# Sheet2.net
KiCad netlist of a schematic drawn in Altium Designer
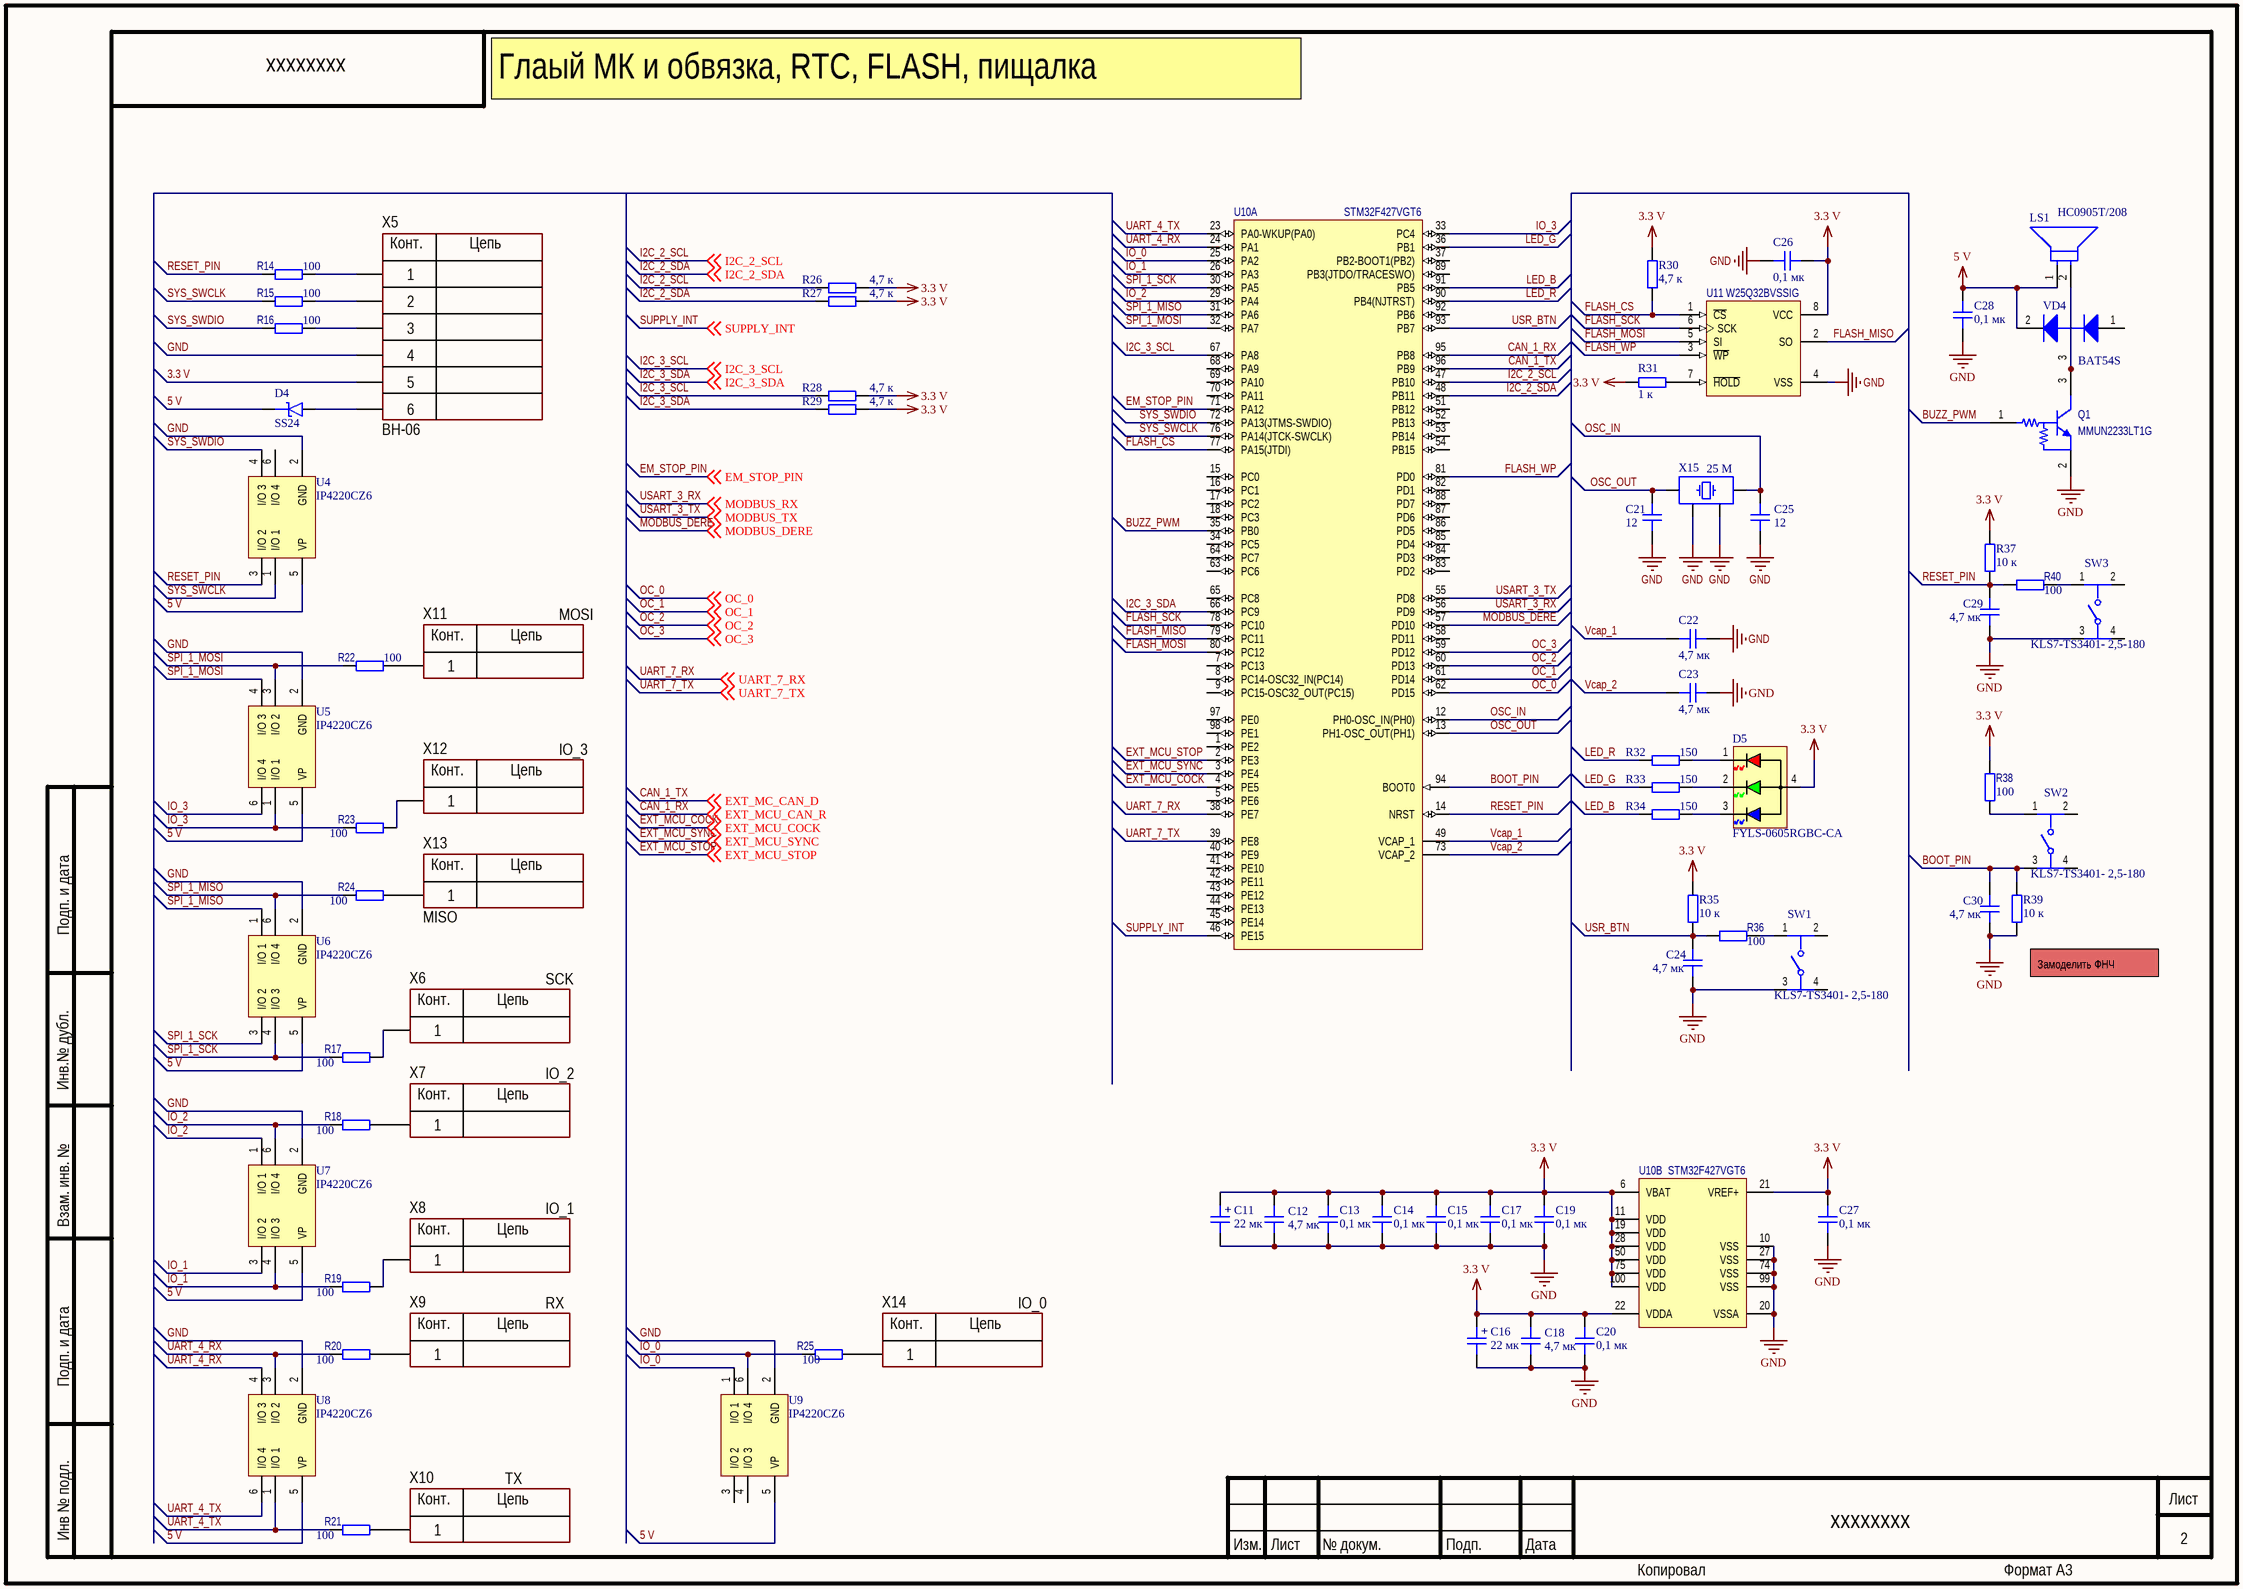
[diagram p0: Sheet2.SchDoc]

(export (version "E")
  (design (tool "Eeschema 10.0.6"))
  (components
    (comp (ref "C11")
      (value "22 мк")
      (footprint "TANTAL_B")
      (description "Capacitor SMD Aluminium Electrolytic 16x16.5mm 25V")
      (fields (field (name "VOLTAGE") "6,3"))
      (libsource (lib "Schematic-Lib-PhilsLab") (part "CAP_ALEL_16x16.5_25V"))
    )
    (comp (ref "C12")
      (value "4,7 мк")
      (footprint "CAP_0805")
      (description "Capacitor SMD 0805")
      (libsource (lib "Schematic-Lib-PhilsLab") (part "CAP_0805"))
    )
    (comp (ref "C13")
      (value "0,1 мк")
      (footprint "CAP_0603")
      (description "Capacitor SMD 0603")
      (libsource (lib "Schematic-Lib-PhilsLab") (part "CAP_0603"))
    )
    (comp (ref "C14")
      (value "0,1 мк")
      (footprint "CAP_0603")
      (description "Capacitor SMD 0603")
      (libsource (lib "Schematic-Lib-PhilsLab") (part "CAP_0603"))
    )
    (comp (ref "C15")
      (value "0,1 мк")
      (footprint "CAP_0603")
      (description "Capacitor SMD 0603")
      (libsource (lib "Schematic-Lib-PhilsLab") (part "CAP_0603"))
    )
    (comp (ref "C16")
      (value "22 мк")
      (footprint "TANTAL_B")
      (description "Capacitor SMD Aluminium Electrolytic 16x16.5mm 25V")
      (fields (field (name "VOLTAGE") "6,3"))
      (libsource (lib "Schematic-Lib-PhilsLab") (part "CAP_ALEL_16x16.5_25V"))
    )
    (comp (ref "C17")
      (value "0,1 мк")
      (footprint "CAP_0603")
      (description "Capacitor SMD 0603")
      (libsource (lib "Schematic-Lib-PhilsLab") (part "CAP_0603"))
    )
    (comp (ref "C18")
      (value "4,7 мк")
      (footprint "CAP_0805")
      (description "Capacitor SMD 0805")
      (libsource (lib "Schematic-Lib-PhilsLab") (part "CAP_0805"))
    )
    (comp (ref "C19")
      (value "0,1 мк")
      (footprint "CAP_0603")
      (description "Capacitor SMD 0603")
      (libsource (lib "Schematic-Lib-PhilsLab") (part "CAP_0603"))
    )
    (comp (ref "C20")
      (value "0,1 мк")
      (footprint "CAP_0603")
      (description "Capacitor SMD 0603")
      (libsource (lib "Schematic-Lib-PhilsLab") (part "CAP_0603"))
    )
    (comp (ref "C21")
      (value "12")
      (footprint "CAP_0603")
      (description "Capacitor SMD 0603")
      (libsource (lib "Schematic-Lib-PhilsLab") (part "CAP_0603"))
    )
    (comp (ref "C22")
      (value "4,7 мк")
      (footprint "CAP_0805")
      (description "Capacitor SMD 0805")
      (libsource (lib "Schematic-Lib-PhilsLab") (part "CAP_0805"))
    )
    (comp (ref "C23")
      (value "4,7 мк")
      (footprint "CAP_0805")
      (description "Capacitor SMD 0805")
      (libsource (lib "Schematic-Lib-PhilsLab") (part "CAP_0805"))
    )
    (comp (ref "C24")
      (value "4,7 мк")
      (footprint "CAP_0805")
      (description "Capacitor SMD 0805")
      (libsource (lib "Schematic-Lib-PhilsLab") (part "CAP_0805"))
    )
    (comp (ref "C25")
      (value "12")
      (footprint "CAP_0603")
      (description "Capacitor SMD 0603")
      (libsource (lib "Schematic-Lib-PhilsLab") (part "CAP_0603"))
    )
    (comp (ref "C26")
      (value "0,1 мк")
      (footprint "CAP_0603")
      (description "Capacitor SMD 0603")
      (libsource (lib "Schematic-Lib-PhilsLab") (part "CAP_0603"))
    )
    (comp (ref "C27")
      (value "0,1 мк")
      (footprint "CAP_0603")
      (description "Capacitor SMD 0603")
      (libsource (lib "Schematic-Lib-PhilsLab") (part "CAP_0603"))
    )
    (comp (ref "C28")
      (value "0,1 мк")
      (footprint "CAP_0603")
      (description "Capacitor SMD 0603")
      (libsource (lib "Schematic-Lib-PhilsLab") (part "CAP_0603"))
    )
    (comp (ref "C29")
      (value "4,7 мк")
      (footprint "CAP_0805")
      (description "Capacitor SMD 0805")
      (libsource (lib "Schematic-Lib-PhilsLab") (part "CAP_0805"))
    )
    (comp (ref "C30")
      (value "4,7 мк")
      (footprint "CAP_0805")
      (description "Capacitor SMD 0805")
      (libsource (lib "Schematic-Lib-PhilsLab") (part "CAP_0805"))
    )
    (comp (ref "D4")
      (value "SS24")
      (footprint "DO-214AC-2 (SMA)")
      (description "Diode Schottky SMD SMA (DO-214AA)")
      (libsource (lib "Schematic-Lib-PhilsLab") (part "D_SCHOTTKY_SMA"))
    )
    (comp (ref "D5")
      (value "FYLS-0605RGBC-CA")
      (footprint "150080M153000")
      (description "RGB LED Common Anode SMD Diffused 0805 Top View")
      (libsource (lib "Schematic-Lib-PhilsLab") (part "150080M153000"))
    )
    (comp (ref "LS1")
      (value "HC0905T/208")
      (footprint "FP-SD1209-MFG")
      (description "AUDIO MAGNETIC XDCR 3-6V TH")
      (libsource (lib "Altium Content Vault") (part "1973c4b650225fd2ddacaff6b763965"))
    )
    (comp (ref "Q1")
      (value "MMUN2233LT1G")
      (footprint "ONSC-SOT-23-3-318-08_V")
      (libsource (lib "Altium Content Vault") (part "ONSC-BRT-NPN-B1E2C3-3"))
    )
    (comp (ref "R14")
      (value "100")
      (footprint "RES_0603")
      (description "Resistor SMD 0603")
      (libsource (lib "Schematic-Lib-PhilsLab") (part "RES_0603"))
    )
    (comp (ref "R15")
      (value "100")
      (footprint "RES_0603")
      (description "Resistor SMD 0603")
      (libsource (lib "Schematic-Lib-PhilsLab") (part "RES_0603"))
    )
    (comp (ref "R16")
      (value "100")
      (footprint "RES_0603")
      (description "Resistor SMD 0603")
      (libsource (lib "Schematic-Lib-PhilsLab") (part "RES_0603"))
    )
    (comp (ref "R17")
      (value "100")
      (footprint "RES_0603")
      (description "Resistor SMD 0603")
      (libsource (lib "Schematic-Lib-PhilsLab") (part "RES_0603"))
    )
    (comp (ref "R18")
      (value "100")
      (footprint "RES_0603")
      (description "Resistor SMD 0603")
      (libsource (lib "Schematic-Lib-PhilsLab") (part "RES_0603"))
    )
    (comp (ref "R19")
      (value "100")
      (footprint "RES_0603")
      (description "Resistor SMD 0603")
      (libsource (lib "Schematic-Lib-PhilsLab") (part "RES_0603"))
    )
    (comp (ref "R20")
      (value "100")
      (footprint "RES_0603")
      (description "Resistor SMD 0603")
      (libsource (lib "Schematic-Lib-PhilsLab") (part "RES_0603"))
    )
    (comp (ref "R21")
      (value "100")
      (footprint "RES_0603")
      (description "Resistor SMD 0603")
      (libsource (lib "Schematic-Lib-PhilsLab") (part "RES_0603"))
    )
    (comp (ref "R22")
      (value "100")
      (footprint "RES_0603")
      (description "Resistor SMD 0603")
      (libsource (lib "Schematic-Lib-PhilsLab") (part "RES_0603"))
    )
    (comp (ref "R23")
      (value "100")
      (footprint "RES_0603")
      (description "Resistor SMD 0603")
      (libsource (lib "Schematic-Lib-PhilsLab") (part "RES_0603"))
    )
    (comp (ref "R24")
      (value "100")
      (footprint "RES_0603")
      (description "Resistor SMD 0603")
      (libsource (lib "Schematic-Lib-PhilsLab") (part "RES_0603"))
    )
    (comp (ref "R25")
      (value "100")
      (footprint "RES_0603")
      (description "Resistor SMD 0603")
      (libsource (lib "Schematic-Lib-PhilsLab") (part "RES_0603"))
    )
    (comp (ref "R26")
      (value "4,7 к")
      (footprint "RES_0603")
      (description "Resistor SMD 0603")
      (libsource (lib "Schematic-Lib-PhilsLab") (part "RES_0603"))
    )
    (comp (ref "R27")
      (value "4,7 к")
      (footprint "RES_0603")
      (description "Resistor SMD 0603")
      (libsource (lib "Schematic-Lib-PhilsLab") (part "RES_0603"))
    )
    (comp (ref "R28")
      (value "4,7 к")
      (footprint "RES_0603")
      (description "Resistor SMD 0603")
      (libsource (lib "Schematic-Lib-PhilsLab") (part "RES_0603"))
    )
    (comp (ref "R29")
      (value "4,7 к")
      (footprint "RES_0603")
      (description "Resistor SMD 0603")
      (libsource (lib "Schematic-Lib-PhilsLab") (part "RES_0603"))
    )
    (comp (ref "R30")
      (value "4,7 к")
      (footprint "RES_0603")
      (description "Resistor SMD 0603")
      (libsource (lib "Schematic-Lib-PhilsLab") (part "RES_0603"))
    )
    (comp (ref "R31")
      (value "1 к")
      (footprint "RES_0603")
      (description "Resistor SMD 0603")
      (libsource (lib "Schematic-Lib-PhilsLab") (part "RES_0603"))
    )
    (comp (ref "R32")
      (value "150")
      (footprint "RES_0603")
      (description "Resistor SMD 0603")
      (libsource (lib "Schematic-Lib-PhilsLab") (part "RES_0603"))
    )
    (comp (ref "R33")
      (value "150")
      (footprint "RES_0603")
      (description "Resistor SMD 0603")
      (libsource (lib "Schematic-Lib-PhilsLab") (part "RES_0603"))
    )
    (comp (ref "R34")
      (value "150")
      (footprint "RES_0603")
      (description "Resistor SMD 0603")
      (libsource (lib "Schematic-Lib-PhilsLab") (part "RES_0603"))
    )
    (comp (ref "R35")
      (value "10 к")
      (footprint "RES_0603")
      (description "Resistor SMD 0603")
      (libsource (lib "Schematic-Lib-PhilsLab") (part "RES_0603"))
    )
    (comp (ref "R36")
      (value "100")
      (footprint "RES_0603")
      (description "Resistor SMD 0603")
      (libsource (lib "Schematic-Lib-PhilsLab") (part "RES_0603"))
    )
    (comp (ref "R37")
      (value "10 к")
      (footprint "RES_0603")
      (description "Resistor SMD 0603")
      (libsource (lib "Schematic-Lib-PhilsLab") (part "RES_0603"))
    )
    (comp (ref "R38")
      (value "100")
      (footprint "RES_0603")
      (description "Resistor SMD 0603")
      (libsource (lib "Schematic-Lib-PhilsLab") (part "RES_0603"))
    )
    (comp (ref "R39")
      (value "10 к")
      (footprint "RES_0603")
      (description "Resistor SMD 0603")
      (libsource (lib "Schematic-Lib-PhilsLab") (part "RES_0603"))
    )
    (comp (ref "R40")
      (value "100")
      (footprint "RES_0603")
      (description "Resistor SMD 0603")
      (libsource (lib "Schematic-Lib-PhilsLab") (part "RES_0603"))
    )
    (comp (ref "SW1")
      (value "KLS7-TS3401- 2,5-180")
      (footprint "FP-PTS810_SJG_250_SMTR_LF-MFG")
      (description "SWITCH TACTILE SPST-NO 0.05A 16V")
      (libsource (lib "Altium Content Vault") (part "1adf0dd01260c80cf25a44bfd6b99ba"))
    )
    (comp (ref "SW2")
      (value "KLS7-TS3401- 2,5-180")
      (footprint "FP-PTS810_SJG_250_SMTR_LF-MFG")
      (description "SWITCH TACTILE SPST-NO 0.05A 16V")
      (libsource (lib "Altium Content Vault") (part "1adf0dd01260c80cf25a44bfd6b99ba"))
    )
    (comp (ref "SW3")
      (value "KLS7-TS3401- 2,5-180")
      (footprint "FP-PTS810_SJG_250_SMTR_LF-MFG")
      (description "SWITCH TACTILE SPST-NO 0.05A 16V")
      (libsource (lib "Altium Content Vault") (part "1adf0dd01260c80cf25a44bfd6b99ba"))
    )
    (comp (ref "U4")
      (value "IP4220CZ6")
      (footprint "NXP-SOT457_L")
      (libsource (lib "") (part "NXP-IP4220CZ6-6_1"))
    )
    (comp (ref "U5")
      (value "IP4220CZ6")
      (footprint "NXP-SOT457_L")
      (libsource (lib "Altium Content Vault") (part "NXP-IP4220CZ6-6"))
    )
    (comp (ref "U6")
      (value "IP4220CZ6")
      (footprint "NXP-SOT457_L")
      (libsource (lib "") (part "NXP-IP4220CZ6-6_2"))
    )
    (comp (ref "U7")
      (value "IP4220CZ6")
      (footprint "NXP-SOT457_L")
      (libsource (lib "") (part "NXP-IP4220CZ6-6_2"))
    )
    (comp (ref "U8")
      (value "IP4220CZ6")
      (footprint "NXP-SOT457_L")
      (libsource (lib "Altium Content Vault") (part "NXP-IP4220CZ6-6"))
    )
    (comp (ref "U9")
      (value "IP4220CZ6")
      (footprint "NXP-SOT457_L")
      (libsource (lib "") (part "NXP-IP4220CZ6-6_2"))
    )
    (comp (ref "U10")
      (value "STM32F427VGT6")
      (footprint "STM-LQFP100_M")
      (libsource (lib "Altium Content Vault") (part "MC-ARM-STM32F4X7-SQ100"))
    )
    (comp (ref "U11")
      (value "W25Q32BVSSIG")
      (footprint "SOIJ-SM8_L")
      (description "1 Mbit SPI Bus Serial EEPROM, 8-Pin SOIC, Industrial Temperature, Tape and Reel")
      (libsource (lib "Altium Content Vault") (part "MEM-SEEPROM-25AA1024-8"))
    )
    (comp (ref "VD4")
      (value "BAT54S")
      (footprint "ONSC-SOT-323-3-419-04_V")
      (libsource (lib "Altium Content Vault") (part "ONSC-D-A1K2C3-3"))
    )
    (comp (ref "X5")
      (value "BH-06")
      (footprint "CON: IDC-6MS")
      (libsource (lib "Connectors") (part "6-Connector"))
    )
    (comp (ref "X6")
      (value "SCK")
      (footprint "CON: PADS 1x1mm")
      (libsource (lib "Connectors") (part "1-Connector"))
    )
    (comp (ref "X7")
      (value "IO_2")
      (footprint "CON: PADS 1x1mm")
      (libsource (lib "Connectors") (part "1-Connector"))
    )
    (comp (ref "X8")
      (value "IO_1")
      (footprint "CON: PADS 1x1mm")
      (libsource (lib "Connectors") (part "1-Connector"))
    )
    (comp (ref "X9")
      (value "RX")
      (footprint "CON: PADS 1x1mm")
      (libsource (lib "Connectors") (part "1-Connector"))
    )
    (comp (ref "X10")
      (value "TX")
      (footprint "CON: PADS 1x1mm")
      (libsource (lib "Connectors") (part "1-Connector"))
    )
    (comp (ref "X11")
      (value "MOSI")
      (footprint "CON: PADS 1x1mm")
      (libsource (lib "Connectors") (part "1-Connector"))
    )
    (comp (ref "X12")
      (value "IO_3")
      (footprint "CON: PADS 1x1mm")
      (libsource (lib "Connectors") (part "1-Connector"))
    )
    (comp (ref "X13")
      (value "MISO")
      (footprint "CON: PADS 1x1mm")
      (libsource (lib "Connectors") (part "1-Connector"))
    )
    (comp (ref "X14")
      (value "IO_0")
      (footprint "CON: PADS 1x1mm")
      (libsource (lib "Connectors") (part "1-Connector"))
    )
    (comp (ref "X15")
      (value "25 M")
      (footprint "XTAL_3225")
      (description "Crystal SMD 24MHz 10PPM 7pF 3225")
      (libsource (lib "Schematic-Lib-PhilsLab") (part "TSX-3225_24.0000MF15X-AC"))
    )
  )
  (nets
    (net (code "1") (name "/BOOT_PIN") (class "Default")
      (node (ref "C30") (pin "1") (pinfunction "1_1") (pintype "passive"))
      (node (ref "R39") (pin "1") (pinfunction "1_1") (pintype "passive"))
      (node (ref "SW2") (pin "3") (pinfunction "3_3") (pintype "passive"))
      (node (ref "U10") (pin "94") (pinfunction "BOOT0_94") (pintype "input"))
    )
    (net (code "2") (name "/BUZZ_PWM") (class "Default")
      (node (ref "Q1") (pin "1") (pinfunction "B_1") (pintype "passive"))
      (node (ref "U10") (pin "35") (pinfunction "PB0_35") (pintype "bidirectional"))
    )
    (net (code "3") (name "/FLASH_CS") (class "Default")
      (node (ref "R30") (pin "1") (pinfunction "1_1") (pintype "passive"))
      (node (ref "U10") (pin "77") (pinfunction "PA15(JTDI)_77") (pintype "bidirectional"))
      (node (ref "U11") (pin "1") (pinfunction "~{CS}_1") (pintype "input"))
    )
    (net (code "4") (name "/FLASH_MISO") (class "Default")
      (node (ref "U10") (pin "79") (pinfunction "PC11_79") (pintype "bidirectional"))
      (node (ref "U11") (pin "2") (pinfunction "SO_2") (pintype "tri_state"))
    )
    (net (code "5") (name "/FLASH_MOSI") (class "Default")
      (node (ref "U10") (pin "80") (pinfunction "PC12_80") (pintype "bidirectional"))
      (node (ref "U11") (pin "5") (pinfunction "SI_5") (pintype "input"))
    )
    (net (code "6") (name "/FLASH_SCK") (class "Default")
      (node (ref "U10") (pin "78") (pinfunction "PC10_78") (pintype "bidirectional"))
      (node (ref "U11") (pin "6") (pinfunction "SCK_6") (pintype "input"))
    )
    (net (code "7") (name "/FLASH_WP") (class "Default")
      (node (ref "U10") (pin "81") (pinfunction "PD0_81") (pintype "bidirectional"))
      (node (ref "U11") (pin "3") (pinfunction "~{WP}_3") (pintype "input"))
    )
    (net (code "8") (name "/IO_0") (class "Default")
      (node (ref "R25") (pin "1") (pinfunction "1_1") (pintype "passive"))
      (node (ref "U10") (pin "25") (pinfunction "PA2_25") (pintype "bidirectional"))
      (node (ref "U9") (pin "1") (pinfunction "I/O_1_1") (pintype "passive"))
      (node (ref "U9") (pin "6") (pinfunction "I/O_4_6") (pintype "passive"))
    )
    (net (code "9") (name "/IO_1") (class "Default")
      (node (ref "R19") (pin "1") (pinfunction "1_1") (pintype "passive"))
      (node (ref "U10") (pin "26") (pinfunction "PA3_26") (pintype "bidirectional"))
      (node (ref "U7") (pin "3") (pinfunction "I/O_2_3") (pintype "passive"))
      (node (ref "U7") (pin "4") (pinfunction "I/O_3_4") (pintype "passive"))
    )
    (net (code "10") (name "/IO_2") (class "Default")
      (node (ref "R18") (pin "1") (pinfunction "1_1") (pintype "passive"))
      (node (ref "U10") (pin "29") (pinfunction "PA4_29") (pintype "bidirectional"))
      (node (ref "U7") (pin "1") (pinfunction "I/O_1_1") (pintype "passive"))
      (node (ref "U7") (pin "6") (pinfunction "I/O_4_6") (pintype "passive"))
    )
    (net (code "11") (name "/IO_3") (class "Default")
      (node (ref "R23") (pin "1") (pinfunction "1_1") (pintype "passive"))
      (node (ref "U10") (pin "33") (pinfunction "PC4_33") (pintype "bidirectional"))
      (node (ref "U5") (pin "1") (pinfunction "I/O_1_1") (pintype "passive"))
      (node (ref "U5") (pin "6") (pinfunction "I/O_4_6") (pintype "passive"))
    )
    (net (code "12") (name "/LED_B") (class "Default")
      (node (ref "R34") (pin "1") (pinfunction "1_1") (pintype "passive"))
      (node (ref "U10") (pin "91") (pinfunction "PB5_91") (pintype "bidirectional"))
    )
    (net (code "13") (name "/LED_G") (class "Default")
      (node (ref "R33") (pin "1") (pinfunction "1_1") (pintype "passive"))
      (node (ref "U10") (pin "36") (pinfunction "PB1_36") (pintype "bidirectional"))
    )
    (net (code "14") (name "/LED_R") (class "Default")
      (node (ref "R32") (pin "1") (pinfunction "1_1") (pintype "passive"))
      (node (ref "U10") (pin "90") (pinfunction "PB4(NJTRST)_90") (pintype "bidirectional"))
    )
    (net (code "15") (name "/OSC_IN") (class "Default")
      (node (ref "C25") (pin "1") (pinfunction "1_1") (pintype "passive"))
      (node (ref "U10") (pin "12") (pinfunction "PH0-OSC_IN(PH0)_12") (pintype "bidirectional"))
      (node (ref "X15") (pin "3") (pinfunction "3_3") (pintype "passive"))
    )
    (net (code "16") (name "/OSC_OUT") (class "Default")
      (node (ref "C21") (pin "1") (pinfunction "1_1") (pintype "passive"))
      (node (ref "U10") (pin "13") (pinfunction "PH1-OSC_OUT(PH1)_13") (pintype "bidirectional"))
      (node (ref "X15") (pin "1") (pinfunction "1_1") (pintype "passive"))
    )
    (net (code "17") (name "/RESET_PIN") (class "Default")
      (node (ref "C29") (pin "1") (pinfunction "1_1") (pintype "passive"))
      (node (ref "R14") (pin "1") (pinfunction "1_1") (pintype "passive"))
      (node (ref "R37") (pin "2") (pinfunction "2_2") (pintype "passive"))
      (node (ref "R40") (pin "2") (pinfunction "2_2") (pintype "passive"))
      (node (ref "U10") (pin "14") (pinfunction "NRST_14") (pintype "bidirectional"))
      (node (ref "U4") (pin "3") (pinfunction "I/O_2_3") (pintype "passive"))
    )
    (net (code "18") (name "/SPI_1_MISO") (class "Default")
      (node (ref "R24") (pin "1") (pinfunction "1_1") (pintype "passive"))
      (node (ref "U10") (pin "31") (pinfunction "PA6_31") (pintype "bidirectional"))
      (node (ref "U6") (pin "1") (pinfunction "I/O_1_1") (pintype "passive"))
      (node (ref "U6") (pin "6") (pinfunction "I/O_4_6") (pintype "passive"))
    )
    (net (code "19") (name "/SPI_1_MOSI") (class "Default")
      (node (ref "R22") (pin "1") (pinfunction "1_1") (pintype "passive"))
      (node (ref "U10") (pin "32") (pinfunction "PA7_32") (pintype "bidirectional"))
      (node (ref "U5") (pin "3") (pinfunction "I/O_2_3") (pintype "passive"))
      (node (ref "U5") (pin "4") (pinfunction "I/O_3_4") (pintype "passive"))
    )
    (net (code "20") (name "/SPI_1_SCK") (class "Default")
      (node (ref "R17") (pin "1") (pinfunction "1_1") (pintype "passive"))
      (node (ref "U10") (pin "30") (pinfunction "PA5_30") (pintype "bidirectional"))
      (node (ref "U6") (pin "3") (pinfunction "I/O_2_3") (pintype "passive"))
      (node (ref "U6") (pin "4") (pinfunction "I/O_3_4") (pintype "passive"))
    )
    (net (code "21") (name "/SYS_SWCLK") (class "Default")
      (node (ref "R15") (pin "1") (pinfunction "1_1") (pintype "passive"))
      (node (ref "U10") (pin "76") (pinfunction "PA14(JTCK-SWCLK)_76") (pintype "bidirectional"))
      (node (ref "U4") (pin "1") (pinfunction "I/O_1_1") (pintype "passive"))
    )
    (net (code "22") (name "/SYS_SWDIO") (class "Default")
      (node (ref "R16") (pin "1") (pinfunction "1_1") (pintype "passive"))
      (node (ref "U10") (pin "72") (pinfunction "PA13(JTMS-SWDIO)_72") (pintype "bidirectional"))
      (node (ref "U4") (pin "4") (pinfunction "I/O_3_4") (pintype "passive"))
    )
    (net (code "23") (name "/UART_4_RX") (class "Default")
      (node (ref "R20") (pin "1") (pinfunction "1_1") (pintype "passive"))
      (node (ref "U10") (pin "24") (pinfunction "PA1_24") (pintype "bidirectional"))
      (node (ref "U8") (pin "3") (pinfunction "I/O_2_3") (pintype "passive"))
      (node (ref "U8") (pin "4") (pinfunction "I/O_3_4") (pintype "passive"))
    )
    (net (code "24") (name "/UART_4_TX") (class "Default")
      (node (ref "R21") (pin "1") (pinfunction "1_1") (pintype "passive"))
      (node (ref "U10") (pin "23") (pinfunction "PA0-WKUP(PA0)_23") (pintype "bidirectional"))
      (node (ref "U8") (pin "1") (pinfunction "I/O_1_1") (pintype "passive"))
      (node (ref "U8") (pin "6") (pinfunction "I/O_4_6") (pintype "passive"))
    )
    (net (code "25") (name "/USR_BTN") (class "Default")
      (node (ref "C24") (pin "1") (pinfunction "1_1") (pintype "passive"))
      (node (ref "R35") (pin "2") (pinfunction "2_2") (pintype "passive"))
      (node (ref "R36") (pin "2") (pinfunction "2_2") (pintype "passive"))
      (node (ref "U10") (pin "93") (pinfunction "PB7_93") (pintype "bidirectional"))
    )
    (net (code "26") (name "/Vcap_1") (class "Default")
      (node (ref "C22") (pin "2") (pinfunction "2_2") (pintype "passive"))
      (node (ref "U10") (pin "49") (pinfunction "VCAP_1_49") (pintype "power_in"))
    )
    (net (code "27") (name "/Vcap_2") (class "Default")
      (node (ref "C23") (pin "2") (pinfunction "2_2") (pintype "passive"))
      (node (ref "U10") (pin "73") (pinfunction "VCAP_2_73") (pintype "power_in"))
    )
    (net (code "28") (name "3.3 V") (class "Default")
      (node (ref "C11") (pin "1") (pinfunction "1_1") (pintype "passive"))
      (node (ref "C12") (pin "1") (pinfunction "1_1") (pintype "passive"))
      (node (ref "C13") (pin "1") (pinfunction "1_1") (pintype "passive"))
      (node (ref "C14") (pin "1") (pinfunction "1_1") (pintype "passive"))
      (node (ref "C15") (pin "1") (pinfunction "1_1") (pintype "passive"))
      (node (ref "C16") (pin "1") (pinfunction "1_1") (pintype "passive"))
      (node (ref "C17") (pin "1") (pinfunction "1_1") (pintype "passive"))
      (node (ref "C18") (pin "1") (pinfunction "1_1") (pintype "passive"))
      (node (ref "C19") (pin "1") (pinfunction "1_1") (pintype "passive"))
      (node (ref "C20") (pin "1") (pinfunction "1_1") (pintype "passive"))
      (node (ref "C26") (pin "2") (pinfunction "2_2") (pintype "passive"))
      (node (ref "C27") (pin "1") (pinfunction "1_1") (pintype "passive"))
      (node (ref "D5") (pin "4") (pinfunction "AC_4") (pintype "passive"))
      (node (ref "R26") (pin "2") (pinfunction "2_2") (pintype "passive"))
      (node (ref "R27") (pin "2") (pinfunction "2_2") (pintype "passive"))
      (node (ref "R28") (pin "2") (pinfunction "2_2") (pintype "passive"))
      (node (ref "R29") (pin "2") (pinfunction "2_2") (pintype "passive"))
      (node (ref "R30") (pin "2") (pinfunction "2_2") (pintype "passive"))
      (node (ref "R31") (pin "1") (pinfunction "1_1") (pintype "passive"))
      (node (ref "R35") (pin "1") (pinfunction "1_1") (pintype "passive"))
      (node (ref "R37") (pin "1") (pinfunction "1_1") (pintype "passive"))
      (node (ref "R38") (pin "2") (pinfunction "2_2") (pintype "passive"))
      (node (ref "U10") (pin "100") (pinfunction "VDD_100") (pintype "power_in"))
      (node (ref "U10") (pin "11") (pinfunction "VDD_11") (pintype "power_in"))
      (node (ref "U10") (pin "19") (pinfunction "VDD_19") (pintype "power_in"))
      (node (ref "U10") (pin "21") (pinfunction "VREF+_21") (pintype "power_in"))
      (node (ref "U10") (pin "22") (pinfunction "VDDA_22") (pintype "power_in"))
      (node (ref "U10") (pin "28") (pinfunction "VDD_28") (pintype "power_in"))
      (node (ref "U10") (pin "50") (pinfunction "VDD_50") (pintype "power_in"))
      (node (ref "U10") (pin "6") (pinfunction "VBAT_6") (pintype "power_in"))
      (node (ref "U10") (pin "75") (pinfunction "VDD_75") (pintype "power_in"))
      (node (ref "U11") (pin "8") (pinfunction "VCC_8") (pintype "power_in"))
      (node (ref "X5") (pin "5") (pinfunction "5_5") (pintype "power_in"))
    )
    (net (code "29") (name "5 V") (class "Default")
      (node (ref "C28") (pin "1") (pinfunction "1_1") (pintype "passive"))
      (node (ref "D4") (pin "K") (pinfunction "K_K") (pintype "passive"))
      (node (ref "LS1") (pin "1") (pinfunction "C_1") (pintype "passive"))
      (node (ref "U4") (pin "5") (pinfunction "VP_5") (pintype "power_in"))
      (node (ref "U5") (pin "5") (pinfunction "VP_5") (pintype "power_in"))
      (node (ref "U6") (pin "5") (pinfunction "VP_5") (pintype "power_in"))
      (node (ref "U7") (pin "5") (pinfunction "VP_5") (pintype "power_in"))
      (node (ref "U8") (pin "5") (pinfunction "VP_5") (pintype "power_in"))
      (node (ref "U9") (pin "5") (pinfunction "VP_5") (pintype "power_in"))
      (node (ref "VD4") (pin "2") (pinfunction "K_2") (pintype "passive"))
    )
    (net (code "30") (name "EM_STOP_PIN") (class "Default")
      (node (ref "U10") (pin "71") (pinfunction "PA12_71") (pintype "bidirectional"))
    )
    (net (code "31") (name "EXT_MCU_CAN_R") (class "Default")
      (node (ref "U10") (pin "95") (pinfunction "PB8_95") (pintype "bidirectional"))
    )
    (net (code "32") (name "EXT_MCU_COCK") (class "Default")
      (node (ref "U10") (pin "4") (pinfunction "PE5_4") (pintype "bidirectional"))
    )
    (net (code "33") (name "EXT_MCU_STOP") (class "Default")
      (node (ref "U10") (pin "2") (pinfunction "PE3_2") (pintype "bidirectional"))
    )
    (net (code "34") (name "EXT_MCU_SYNC") (class "Default")
      (node (ref "U10") (pin "3") (pinfunction "PE4_3") (pintype "bidirectional"))
    )
    (net (code "35") (name "EXT_MC_CAN_D") (class "Default")
      (node (ref "U10") (pin "96") (pinfunction "PB9_96") (pintype "bidirectional"))
    )
    (net (code "36") (name "GND") (class "Default")
      (node (ref "C11") (pin "2") (pinfunction "2_2") (pintype "passive"))
      (node (ref "C12") (pin "2") (pinfunction "2_2") (pintype "passive"))
      (node (ref "C13") (pin "2") (pinfunction "2_2") (pintype "passive"))
      (node (ref "C14") (pin "2") (pinfunction "2_2") (pintype "passive"))
      (node (ref "C15") (pin "2") (pinfunction "2_2") (pintype "passive"))
      (node (ref "C16") (pin "2") (pinfunction "2_2") (pintype "passive"))
      (node (ref "C17") (pin "2") (pinfunction "2_2") (pintype "passive"))
      (node (ref "C18") (pin "2") (pinfunction "2_2") (pintype "passive"))
      (node (ref "C19") (pin "2") (pinfunction "2_2") (pintype "passive"))
      (node (ref "C20") (pin "2") (pinfunction "2_2") (pintype "passive"))
      (node (ref "C21") (pin "2") (pinfunction "2_2") (pintype "passive"))
      (node (ref "C22") (pin "1") (pinfunction "1_1") (pintype "passive"))
      (node (ref "C23") (pin "1") (pinfunction "1_1") (pintype "passive"))
      (node (ref "C24") (pin "2") (pinfunction "2_2") (pintype "passive"))
      (node (ref "C25") (pin "2") (pinfunction "2_2") (pintype "passive"))
      (node (ref "C26") (pin "1") (pinfunction "1_1") (pintype "passive"))
      (node (ref "C27") (pin "2") (pinfunction "2_2") (pintype "passive"))
      (node (ref "C28") (pin "2") (pinfunction "2_2") (pintype "passive"))
      (node (ref "C29") (pin "2") (pinfunction "2_2") (pintype "passive"))
      (node (ref "C30") (pin "2") (pinfunction "2_2") (pintype "passive"))
      (node (ref "Q1") (pin "2") (pinfunction "E_2") (pintype "passive"))
      (node (ref "R39") (pin "2") (pinfunction "2_2") (pintype "passive"))
      (node (ref "SW1") (pin "3") (pinfunction "3_3") (pintype "passive"))
      (node (ref "SW3") (pin "3") (pinfunction "3_3") (pintype "passive"))
      (node (ref "U10") (pin "10") (pinfunction "VSS_10") (pintype "power_in"))
      (node (ref "U10") (pin "20") (pinfunction "VSSA_20") (pintype "power_in"))
      (node (ref "U10") (pin "27") (pinfunction "VSS_27") (pintype "power_in"))
      (node (ref "U10") (pin "74") (pinfunction "VSS_74") (pintype "power_in"))
      (node (ref "U10") (pin "99") (pinfunction "VSS_99") (pintype "power_in"))
      (node (ref "U11") (pin "4") (pinfunction "VSS_4") (pintype "power_in"))
      (node (ref "U4") (pin "2") (pinfunction "GND_2") (pintype "power_in"))
      (node (ref "U5") (pin "2") (pinfunction "GND_2") (pintype "power_in"))
      (node (ref "U6") (pin "2") (pinfunction "GND_2") (pintype "power_in"))
      (node (ref "U7") (pin "2") (pinfunction "GND_2") (pintype "power_in"))
      (node (ref "U8") (pin "2") (pinfunction "GND_2") (pintype "power_in"))
      (node (ref "U9") (pin "2") (pinfunction "GND_2") (pintype "power_in"))
      (node (ref "X15") (pin "2") (pinfunction "2_2") (pintype "passive"))
      (node (ref "X15") (pin "4") (pinfunction "4_4") (pintype "passive"))
      (node (ref "X5") (pin "4") (pinfunction "4_4") (pintype "power_in"))
    )
    (net (code "37") (name "I2C_2_SCL") (class "Default")
      (node (ref "R26") (pin "1") (pinfunction "1_1") (pintype "passive"))
      (node (ref "U10") (pin "47") (pinfunction "PB10_47") (pintype "bidirectional"))
    )
    (net (code "38") (name "I2C_2_SDA") (class "Default")
      (node (ref "R27") (pin "1") (pinfunction "1_1") (pintype "passive"))
      (node (ref "U10") (pin "48") (pinfunction "PB11_48") (pintype "bidirectional"))
    )
    (net (code "39") (name "I2C_3_SCL") (class "Default")
      (node (ref "R28") (pin "1") (pinfunction "1_1") (pintype "passive"))
      (node (ref "U10") (pin "67") (pinfunction "PA8_67") (pintype "bidirectional"))
    )
    (net (code "40") (name "I2C_3_SDA") (class "Default")
      (node (ref "R29") (pin "1") (pinfunction "1_1") (pintype "passive"))
      (node (ref "U10") (pin "66") (pinfunction "PC9_66") (pintype "bidirectional"))
    )
    (net (code "41") (name "MODBUS_DERE") (class "Default")
      (node (ref "U10") (pin "57") (pinfunction "PD10_57") (pintype "bidirectional"))
    )
    (net (code "42") (name "MODBUS_RX") (class "Default")
      (node (ref "U10") (pin "56") (pinfunction "PD9_56") (pintype "bidirectional"))
    )
    (net (code "43") (name "MODBUS_TX") (class "Default")
      (node (ref "U10") (pin "55") (pinfunction "PD8_55") (pintype "bidirectional"))
    )
    (net (code "44") (name "Net-(D4-PadA)") (class "Default")
      (node (ref "D4") (pin "A") (pinfunction "A_A") (pintype "passive"))
      (node (ref "X5") (pin "6") (pinfunction "6_6") (pintype "power_in"))
    )
    (net (code "45") (name "Net-(D5-CB)") (class "Default")
      (node (ref "D5") (pin "3") (pinfunction "CB_3") (pintype "passive"))
      (node (ref "R34") (pin "2") (pinfunction "2_2") (pintype "passive"))
    )
    (net (code "46") (name "Net-(D5-CG)") (class "Default")
      (node (ref "D5") (pin "2") (pinfunction "CG_2") (pintype "passive"))
      (node (ref "R33") (pin "2") (pinfunction "2_2") (pintype "passive"))
    )
    (net (code "47") (name "Net-(D5-CR)") (class "Default")
      (node (ref "D5") (pin "1") (pinfunction "CR_1") (pintype "passive"))
      (node (ref "R32") (pin "2") (pinfunction "2_2") (pintype "passive"))
    )
    (net (code "48") (name "Net-(LS1-A)") (class "Default")
      (node (ref "LS1") (pin "2") (pinfunction "A_2") (pintype "passive"))
      (node (ref "Q1") (pin "3") (pinfunction "C_3") (pintype "passive"))
      (node (ref "VD4") (pin "3") (pinfunction "K/A_3") (pintype "passive"))
    )
    (net (code "49") (name "Net-(R14-Pad2)") (class "Default")
      (node (ref "R14") (pin "2") (pinfunction "2_2") (pintype "passive"))
      (node (ref "X5") (pin "1") (pinfunction "1_1") (pintype "passive"))
    )
    (net (code "50") (name "Net-(R15-Pad2)") (class "Default")
      (node (ref "R15") (pin "2") (pinfunction "2_2") (pintype "passive"))
      (node (ref "X5") (pin "2") (pinfunction "2_2") (pintype "passive"))
    )
    (net (code "51") (name "Net-(R16-Pad2)") (class "Default")
      (node (ref "R16") (pin "2") (pinfunction "2_2") (pintype "passive"))
      (node (ref "X5") (pin "3") (pinfunction "3_3") (pintype "power_in"))
    )
    (net (code "52") (name "Net-(R17-Pad2)") (class "Default")
      (node (ref "R17") (pin "2") (pinfunction "2_2") (pintype "passive"))
      (node (ref "X6") (pin "1") (pinfunction "1_1") (pintype "passive"))
    )
    (net (code "53") (name "Net-(R18-Pad2)") (class "Default")
      (node (ref "R18") (pin "2") (pinfunction "2_2") (pintype "passive"))
      (node (ref "X7") (pin "1") (pinfunction "1_1") (pintype "passive"))
    )
    (net (code "54") (name "Net-(R19-Pad2)") (class "Default")
      (node (ref "R19") (pin "2") (pinfunction "2_2") (pintype "passive"))
      (node (ref "X8") (pin "1") (pinfunction "1_1") (pintype "passive"))
    )
    (net (code "55") (name "Net-(R20-Pad2)") (class "Default")
      (node (ref "R20") (pin "2") (pinfunction "2_2") (pintype "passive"))
      (node (ref "X9") (pin "1") (pinfunction "1_1") (pintype "passive"))
    )
    (net (code "56") (name "Net-(R21-Pad2)") (class "Default")
      (node (ref "R21") (pin "2") (pinfunction "2_2") (pintype "passive"))
      (node (ref "X10") (pin "1") (pinfunction "1_1") (pintype "passive"))
    )
    (net (code "57") (name "Net-(R22-Pad2)") (class "Default")
      (node (ref "R22") (pin "2") (pinfunction "2_2") (pintype "passive"))
      (node (ref "X11") (pin "1") (pinfunction "1_1") (pintype "passive"))
    )
    (net (code "58") (name "Net-(R23-Pad2)") (class "Default")
      (node (ref "R23") (pin "2") (pinfunction "2_2") (pintype "passive"))
      (node (ref "X12") (pin "1") (pinfunction "1_1") (pintype "passive"))
    )
    (net (code "59") (name "Net-(R24-Pad2)") (class "Default")
      (node (ref "R24") (pin "2") (pinfunction "2_2") (pintype "passive"))
      (node (ref "X13") (pin "1") (pinfunction "1_1") (pintype "passive"))
    )
    (net (code "60") (name "Net-(R25-Pad2)") (class "Default")
      (node (ref "R25") (pin "2") (pinfunction "2_2") (pintype "passive"))
      (node (ref "X14") (pin "1") (pinfunction "1_1") (pintype "passive"))
    )
    (net (code "61") (name "Net-(R36-Pad1)") (class "Default")
      (node (ref "R36") (pin "1") (pinfunction "1_1") (pintype "passive"))
      (node (ref "SW1") (pin "1") (pinfunction "1_1") (pintype "passive"))
    )
    (net (code "62") (name "Net-(R38-Pad1)") (class "Default")
      (node (ref "R38") (pin "1") (pinfunction "1_1") (pintype "passive"))
      (node (ref "SW2") (pin "1") (pinfunction "1_1") (pintype "passive"))
    )
    (net (code "63") (name "Net-(R40-Pad1)") (class "Default")
      (node (ref "R40") (pin "1") (pinfunction "1_1") (pintype "passive"))
      (node (ref "SW3") (pin "1") (pinfunction "1_1") (pintype "passive"))
    )
    (net (code "64") (name "Net-(U11-~{HOLD})") (class "Default")
      (node (ref "R31") (pin "2") (pinfunction "2_2") (pintype "passive"))
      (node (ref "U11") (pin "7") (pinfunction "~{HOLD}_7") (pintype "input"))
    )
    (net (code "65") (name "OС_0") (class "Default")
      (node (ref "U10") (pin "62") (pinfunction "PD15_62") (pintype "bidirectional"))
    )
    (net (code "66") (name "OС_1") (class "Default")
      (node (ref "U10") (pin "61") (pinfunction "PD14_61") (pintype "bidirectional"))
    )
    (net (code "67") (name "OС_2") (class "Default")
      (node (ref "U10") (pin "60") (pinfunction "PD13_60") (pintype "bidirectional"))
    )
    (net (code "68") (name "OС_3") (class "Default")
      (node (ref "U10") (pin "59") (pinfunction "PD12_59") (pintype "bidirectional"))
    )
    (net (code "69") (name "SUPPLY_INT") (class "Default")
      (node (ref "U10") (pin "46") (pinfunction "PE15_46") (pintype "bidirectional"))
    )
    (net (code "70") (name "UART_7_RX") (class "Default")
      (node (ref "U10") (pin "38") (pinfunction "PE7_38") (pintype "bidirectional"))
    )
    (net (code "71") (name "UART_7_TX") (class "Default")
      (node (ref "U10") (pin "39") (pinfunction "PE8_39") (pintype "bidirectional"))
    )
    (net (code "72") (name "unconnected-(SW1-Pad2)") (class "Default")
      (node (ref "SW1") (pin "2") (pinfunction "2_2") (pintype "passive"))
    )
    (net (code "73") (name "unconnected-(SW1-Pad4)") (class "Default")
      (node (ref "SW1") (pin "4") (pinfunction "4_4") (pintype "passive"))
    )
    (net (code "74") (name "unconnected-(SW2-Pad2)") (class "Default")
      (node (ref "SW2") (pin "2") (pinfunction "2_2") (pintype "passive"))
    )
    (net (code "75") (name "unconnected-(SW2-Pad4)") (class "Default")
      (node (ref "SW2") (pin "4") (pinfunction "4_4") (pintype "passive"))
    )
    (net (code "76") (name "unconnected-(SW3-Pad2)") (class "Default")
      (node (ref "SW3") (pin "2") (pinfunction "2_2") (pintype "passive"))
    )
    (net (code "77") (name "unconnected-(SW3-Pad4)") (class "Default")
      (node (ref "SW3") (pin "4") (pinfunction "4_4") (pintype "passive"))
    )
    (net (code "78") (name "unconnected-(U4-I{slash}O_4-Pad6)") (class "Default")
      (node (ref "U4") (pin "6") (pinfunction "I/O_4_6") (pintype "passive"))
    )
    (net (code "79") (name "unconnected-(U9-I{slash}O_2-Pad3)") (class "Default")
      (node (ref "U9") (pin "3") (pinfunction "I/O_2_3") (pintype "passive"))
    )
    (net (code "80") (name "unconnected-(U9-I{slash}O_3-Pad4)") (class "Default")
      (node (ref "U9") (pin "4") (pinfunction "I/O_3_4") (pintype "passive"))
    )
    (net (code "81") (name "unconnected-(U10A-PA9-Pad68)") (class "Default")
      (node (ref "U10") (pin "68") (pinfunction "PA9_68") (pintype "bidirectional"))
    )
    (net (code "82") (name "unconnected-(U10A-PA10-Pad69)") (class "Default")
      (node (ref "U10") (pin "69") (pinfunction "PA10_69") (pintype "bidirectional"))
    )
    (net (code "83") (name "unconnected-(U10A-PA11-Pad70)") (class "Default")
      (node (ref "U10") (pin "70") (pinfunction "PA11_70") (pintype "bidirectional"))
    )
    (net (code "84") (name "unconnected-(U10A-PB2-BOOT1(PB2)-Pad37)") (class "Default")
      (node (ref "U10") (pin "37") (pinfunction "PB2-BOOT1(PB2)_37") (pintype "bidirectional"))
    )
    (net (code "85") (name "unconnected-(U10A-PB3(JTDO{slash}TRACESWO)-Pad89)") (class "Default")
      (node (ref "U10") (pin "89") (pinfunction "PB3(JTDO/TRACESWO)_89") (pintype "bidirectional"))
    )
    (net (code "86") (name "unconnected-(U10A-PB6-Pad92)") (class "Default")
      (node (ref "U10") (pin "92") (pinfunction "PB6_92") (pintype "bidirectional"))
    )
    (net (code "87") (name "unconnected-(U10A-PB12-Pad51)") (class "Default")
      (node (ref "U10") (pin "51") (pinfunction "PB12_51") (pintype "bidirectional"))
    )
    (net (code "88") (name "unconnected-(U10A-PB13-Pad52)") (class "Default")
      (node (ref "U10") (pin "52") (pinfunction "PB13_52") (pintype "bidirectional"))
    )
    (net (code "89") (name "unconnected-(U10A-PB14-Pad53)") (class "Default")
      (node (ref "U10") (pin "53") (pinfunction "PB14_53") (pintype "bidirectional"))
    )
    (net (code "90") (name "unconnected-(U10A-PB15-Pad54)") (class "Default")
      (node (ref "U10") (pin "54") (pinfunction "PB15_54") (pintype "bidirectional"))
    )
    (net (code "91") (name "unconnected-(U10A-PC0-Pad15)") (class "Default")
      (node (ref "U10") (pin "15") (pinfunction "PC0_15") (pintype "bidirectional"))
    )
    (net (code "92") (name "unconnected-(U10A-PC1-Pad16)") (class "Default")
      (node (ref "U10") (pin "16") (pinfunction "PC1_16") (pintype "bidirectional"))
    )
    (net (code "93") (name "unconnected-(U10A-PC2-Pad17)") (class "Default")
      (node (ref "U10") (pin "17") (pinfunction "PC2_17") (pintype "bidirectional"))
    )
    (net (code "94") (name "unconnected-(U10A-PC3-Pad18)") (class "Default")
      (node (ref "U10") (pin "18") (pinfunction "PC3_18") (pintype "bidirectional"))
    )
    (net (code "95") (name "unconnected-(U10A-PC5-Pad34)") (class "Default")
      (node (ref "U10") (pin "34") (pinfunction "PC5_34") (pintype "bidirectional"))
    )
    (net (code "96") (name "unconnected-(U10A-PC6-Pad63)") (class "Default")
      (node (ref "U10") (pin "63") (pinfunction "PC6_63") (pintype "bidirectional"))
    )
    (net (code "97") (name "unconnected-(U10A-PC7-Pad64)") (class "Default")
      (node (ref "U10") (pin "64") (pinfunction "PC7_64") (pintype "bidirectional"))
    )
    (net (code "98") (name "unconnected-(U10A-PC8-Pad65)") (class "Default")
      (node (ref "U10") (pin "65") (pinfunction "PC8_65") (pintype "bidirectional"))
    )
    (net (code "99") (name "unconnected-(U10A-PC13-Pad7)") (class "Default")
      (node (ref "U10") (pin "7") (pinfunction "PC13_7") (pintype "bidirectional"))
    )
    (net (code "100") (name "unconnected-(U10A-PC14-OSC32_IN(PC14)-Pad8)") (class "Default")
      (node (ref "U10") (pin "8") (pinfunction "PC14-OSC32_IN(PC14)_8") (pintype "bidirectional"))
    )
    (net (code "101") (name "unconnected-(U10A-PC15-OSC32_OUT(PC15)-Pad9)") (class "Default")
      (node (ref "U10") (pin "9") (pinfunction "PC15-OSC32_OUT(PC15)_9") (pintype "bidirectional"))
    )
    (net (code "102") (name "unconnected-(U10A-PD1-Pad82)") (class "Default")
      (node (ref "U10") (pin "82") (pinfunction "PD1_82") (pintype "bidirectional"))
    )
    (net (code "103") (name "unconnected-(U10A-PD2-Pad83)") (class "Default")
      (node (ref "U10") (pin "83") (pinfunction "PD2_83") (pintype "bidirectional"))
    )
    (net (code "104") (name "unconnected-(U10A-PD3-Pad84)") (class "Default")
      (node (ref "U10") (pin "84") (pinfunction "PD3_84") (pintype "bidirectional"))
    )
    (net (code "105") (name "unconnected-(U10A-PD4-Pad85)") (class "Default")
      (node (ref "U10") (pin "85") (pinfunction "PD4_85") (pintype "bidirectional"))
    )
    (net (code "106") (name "unconnected-(U10A-PD5-Pad86)") (class "Default")
      (node (ref "U10") (pin "86") (pinfunction "PD5_86") (pintype "bidirectional"))
    )
    (net (code "107") (name "unconnected-(U10A-PD6-Pad87)") (class "Default")
      (node (ref "U10") (pin "87") (pinfunction "PD6_87") (pintype "bidirectional"))
    )
    (net (code "108") (name "unconnected-(U10A-PD7-Pad88)") (class "Default")
      (node (ref "U10") (pin "88") (pinfunction "PD7_88") (pintype "bidirectional"))
    )
    (net (code "109") (name "unconnected-(U10A-PD11-Pad58)") (class "Default")
      (node (ref "U10") (pin "58") (pinfunction "PD11_58") (pintype "bidirectional"))
    )
    (net (code "110") (name "unconnected-(U10A-PE0-Pad97)") (class "Default")
      (node (ref "U10") (pin "97") (pinfunction "PE0_97") (pintype "bidirectional"))
    )
    (net (code "111") (name "unconnected-(U10A-PE1-Pad98)") (class "Default")
      (node (ref "U10") (pin "98") (pinfunction "PE1_98") (pintype "bidirectional"))
    )
    (net (code "112") (name "unconnected-(U10A-PE2-Pad1)") (class "Default")
      (node (ref "U10") (pin "1") (pinfunction "PE2_1") (pintype "bidirectional"))
    )
    (net (code "113") (name "unconnected-(U10A-PE6-Pad5)") (class "Default")
      (node (ref "U10") (pin "5") (pinfunction "PE6_5") (pintype "bidirectional"))
    )
    (net (code "114") (name "unconnected-(U10A-PE9-Pad40)") (class "Default")
      (node (ref "U10") (pin "40") (pinfunction "PE9_40") (pintype "bidirectional"))
    )
    (net (code "115") (name "unconnected-(U10A-PE10-Pad41)") (class "Default")
      (node (ref "U10") (pin "41") (pinfunction "PE10_41") (pintype "bidirectional"))
    )
    (net (code "116") (name "unconnected-(U10A-PE11-Pad42)") (class "Default")
      (node (ref "U10") (pin "42") (pinfunction "PE11_42") (pintype "bidirectional"))
    )
    (net (code "117") (name "unconnected-(U10A-PE12-Pad43)") (class "Default")
      (node (ref "U10") (pin "43") (pinfunction "PE12_43") (pintype "bidirectional"))
    )
    (net (code "118") (name "unconnected-(U10A-PE13-Pad44)") (class "Default")
      (node (ref "U10") (pin "44") (pinfunction "PE13_44") (pintype "bidirectional"))
    )
    (net (code "119") (name "unconnected-(U10A-PE14-Pad45)") (class "Default")
      (node (ref "U10") (pin "45") (pinfunction "PE14_45") (pintype "bidirectional"))
    )
    (net (code "120") (name "unconnected-(VD4-A-Pad1)") (class "Default")
      (node (ref "VD4") (pin "1") (pinfunction "A_1") (pintype "passive"))
    )
  )
)
